# OsuBoard.net
KiCad netlist of a schematic drawn in Altium Designer
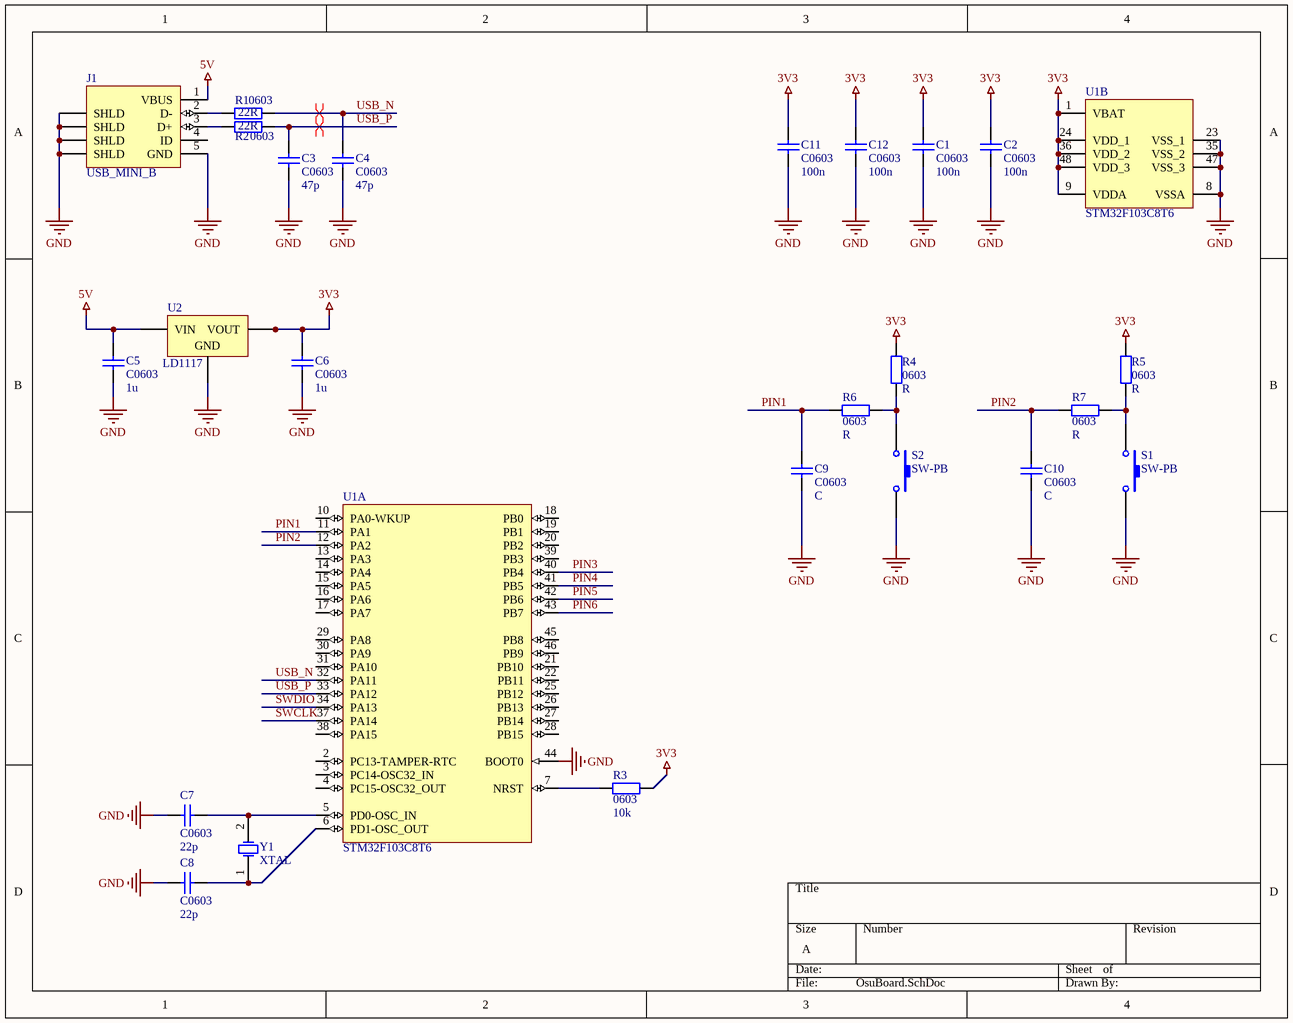
[diagram p0: OsuBoard.SchDoc]

(export (version "E")
  (design (tool "Eeschema 10.0.6"))
  (components
    (comp (ref "C1")
      (value "100n")
      (footprint "C0603")
      (description "Generic capacitor")
      (libsource (lib "_RLC") (part "Cap"))
    )
    (comp (ref "C2")
      (value "100n")
      (footprint "C0603")
      (description "Generic capacitor")
      (libsource (lib "_RLC") (part "Cap"))
    )
    (comp (ref "C3")
      (value "47p")
      (footprint "C0603")
      (description "Generic capacitor")
      (libsource (lib "_RLC") (part "Cap"))
    )
    (comp (ref "C4")
      (value "47p")
      (footprint "C0603")
      (description "Generic capacitor")
      (libsource (lib "_RLC") (part "Cap"))
    )
    (comp (ref "C5")
      (value "1u")
      (footprint "C0603")
      (description "Generic capacitor")
      (libsource (lib "_RLC") (part "Cap"))
    )
    (comp (ref "C6")
      (value "1u")
      (footprint "C0603")
      (description "Generic capacitor")
      (libsource (lib "_RLC") (part "Cap"))
    )
    (comp (ref "C7")
      (value "22p")
      (footprint "C0603")
      (description "Generic capacitor")
      (libsource (lib "_RLC") (part "Cap"))
    )
    (comp (ref "C8")
      (value "22p")
      (footprint "C0603")
      (description "Generic capacitor")
      (libsource (lib "_RLC") (part "Cap"))
    )
    (comp (ref "C9")
      (value "C")
      (footprint "C0603")
      (description "Generic capacitor")
      (libsource (lib "_RLC") (part "Cap"))
    )
    (comp (ref "C10")
      (value "C")
      (footprint "C0603")
      (description "Generic capacitor")
      (libsource (lib "_RLC") (part "Cap"))
    )
    (comp (ref "C11")
      (value "100n")
      (footprint "C0603")
      (description "Generic capacitor")
      (libsource (lib "_RLC") (part "Cap"))
    )
    (comp (ref "C12")
      (value "100n")
      (footprint "C0603")
      (description "Generic capacitor")
      (libsource (lib "_RLC") (part "Cap"))
    )
    (comp (ref "J1")
      (value "USB_MINI_B")
      (footprint "USB_Mini_B_9.3x7.7")
      (description "USB On-The-Go (OTG) Mini-B Receptacle")
      (libsource (lib "_Connectors") (part "USB_MINI_B2"))
    )
    (comp (ref "R1")
      (value "22R")
      (footprint "0603")
      (description "Generic resistor")
      (libsource (lib "") (part "Res_1"))
    )
    (comp (ref "R2")
      (value "22R")
      (footprint "0603")
      (description "Generic resistor")
      (libsource (lib "") (part "Res_1"))
    )
    (comp (ref "R3")
      (value "10k")
      (footprint "0603")
      (description "Generic resistor")
      (libsource (lib "") (part "Res_1"))
    )
    (comp (ref "R4")
      (value "R")
      (footprint "0603")
      (description "Generic resistor")
      (libsource (lib "_RLC") (part "Res"))
    )
    (comp (ref "R5")
      (value "R")
      (footprint "0603")
      (description "Generic resistor")
      (libsource (lib "_RLC") (part "Res"))
    )
    (comp (ref "R6")
      (value "R")
      (footprint "0603")
      (description "Generic resistor")
      (libsource (lib "") (part "Res_1"))
    )
    (comp (ref "R7")
      (value "R")
      (footprint "0603")
      (description "Generic resistor")
      (libsource (lib "") (part "Res_1"))
    )
    (comp (ref "S1")
      (value "SW-PB")
      (footprint "Cherry MX footprint")
      (description "Switch")
      (fields (field (name "PUBLISHER") "Altium Limited"))
      (libsource (lib "Miscellaneous Devices") (part "SW-PB"))
    )
    (comp (ref "S2")
      (value "SW-PB")
      (footprint "Cherry MX footprint")
      (description "Switch")
      (fields (field (name "PUBLISHER") "Altium Limited"))
      (libsource (lib "Miscellaneous Devices") (part "SW-PB"))
    )
    (comp (ref "U1")
      (value "STM32F103C8T6")
      (footprint "QFP_48_0.5_M")
      (libsource (lib "_Microcircuits") (part "STM32F103C8T6"))
    )
    (comp (ref "U2")
      (value "LD1117")
      (footprint "TO-252")
      (description "Low drop positive voltage regulator")
      (libsource (lib "_Microcircuits") (part "LD1117"))
    )
    (comp (ref "Y1")
      (value "XTAL")
      (footprint "HC49")
      (description "Crystal Oscillator")
      (fields (field (name "PUBLISHER") "Altium Limited"))
      (libsource (lib "_Passive") (part "XTAL"))
    )
  )
  (nets
    (net (code "1") (name "/PIN1") (class "Default")
      (node (ref "C9") (pin "1") (pinfunction "1_1") (pintype "passive"))
      (node (ref "R6") (pin "1") (pinfunction "1_1") (pintype "passive"))
      (node (ref "U1") (pin "11") (pinfunction "PA1_11") (pintype "bidirectional"))
    )
    (net (code "2") (name "/PIN2") (class "Default")
      (node (ref "C10") (pin "1") (pinfunction "1_1") (pintype "passive"))
      (node (ref "R7") (pin "1") (pinfunction "1_1") (pintype "passive"))
      (node (ref "U1") (pin "12") (pinfunction "PA2_12") (pintype "bidirectional"))
    )
    (net (code "3") (name "/PIN3") (class "Default")
      (node (ref "U1") (pin "40") (pinfunction "PB4_40") (pintype "bidirectional"))
    )
    (net (code "4") (name "/PIN4") (class "Default")
      (node (ref "U1") (pin "41") (pinfunction "PB5_41") (pintype "bidirectional"))
    )
    (net (code "5") (name "/PIN5") (class "Default")
      (node (ref "U1") (pin "42") (pinfunction "PB6_42") (pintype "bidirectional"))
    )
    (net (code "6") (name "/PIN6") (class "Default")
      (node (ref "U1") (pin "43") (pinfunction "PB7_43") (pintype "bidirectional"))
    )
    (net (code "7") (name "/SWCLK") (class "Default")
      (node (ref "U1") (pin "37") (pinfunction "PA14_37") (pintype "bidirectional"))
    )
    (net (code "8") (name "/SWDIO") (class "Default")
      (node (ref "U1") (pin "34") (pinfunction "PA13_34") (pintype "bidirectional"))
    )
    (net (code "9") (name "/USB_N") (class "Default")
      (node (ref "C4") (pin "1") (pinfunction "1_1") (pintype "passive"))
      (node (ref "R1") (pin "2") (pinfunction "2_2") (pintype "passive"))
      (node (ref "U1") (pin "32") (pinfunction "PA11_32") (pintype "bidirectional"))
    )
    (net (code "10") (name "/USB_P") (class "Default")
      (node (ref "C3") (pin "1") (pinfunction "1_1") (pintype "passive"))
      (node (ref "R2") (pin "2") (pinfunction "2_2") (pintype "passive"))
      (node (ref "U1") (pin "33") (pinfunction "PA12_33") (pintype "bidirectional"))
    )
    (net (code "11") (name "3V3") (class "Default")
      (node (ref "C1") (pin "1") (pinfunction "1_1") (pintype "passive"))
      (node (ref "C11") (pin "1") (pinfunction "1_1") (pintype "passive"))
      (node (ref "C12") (pin "1") (pinfunction "1_1") (pintype "passive"))
      (node (ref "C2") (pin "1") (pinfunction "1_1") (pintype "passive"))
      (node (ref "C6") (pin "1") (pinfunction "1_1") (pintype "passive"))
      (node (ref "R3") (pin "2") (pinfunction "2_2") (pintype "passive"))
      (node (ref "R4") (pin "1") (pinfunction "1_1") (pintype "passive"))
      (node (ref "R5") (pin "1") (pinfunction "1_1") (pintype "passive"))
      (node (ref "U1") (pin "1") (pinfunction "VBAT_1") (pintype "power_in"))
      (node (ref "U1") (pin "24") (pinfunction "VDD_1_24") (pintype "power_in"))
      (node (ref "U1") (pin "36") (pinfunction "VDD_2_36") (pintype "power_in"))
      (node (ref "U1") (pin "48") (pinfunction "VDD_3_48") (pintype "power_in"))
      (node (ref "U1") (pin "9") (pinfunction "VDDA_9") (pintype "power_in"))
      (node (ref "U2") (pin "2") (pinfunction "VOUT_2") (pintype "power_in"))
      (node (ref "U2") (pin "4") (pinfunction "VOUT_4") (pintype "power_in"))
      (node (ref "U2") (pin "5") (pinfunction "VOUT_5") (pintype "power_in"))
      (node (ref "U2") (pin "6") (pinfunction "VOUT_6") (pintype "power_in"))
    )
    (net (code "12") (name "5V") (class "Default")
      (node (ref "C5") (pin "1") (pinfunction "1_1") (pintype "passive"))
      (node (ref "J1") (pin "1") (pinfunction "VBUS_1") (pintype "power_in"))
      (node (ref "U2") (pin "3") (pinfunction "VIN_3") (pintype "power_in"))
    )
    (net (code "13") (name "GND") (class "Default")
      (node (ref "C1") (pin "2") (pinfunction "2_2") (pintype "passive"))
      (node (ref "C10") (pin "2") (pinfunction "2_2") (pintype "passive"))
      (node (ref "C11") (pin "2") (pinfunction "2_2") (pintype "passive"))
      (node (ref "C12") (pin "2") (pinfunction "2_2") (pintype "passive"))
      (node (ref "C2") (pin "2") (pinfunction "2_2") (pintype "passive"))
      (node (ref "C3") (pin "2") (pinfunction "2_2") (pintype "passive"))
      (node (ref "C4") (pin "2") (pinfunction "2_2") (pintype "passive"))
      (node (ref "C5") (pin "2") (pinfunction "2_2") (pintype "passive"))
      (node (ref "C6") (pin "2") (pinfunction "2_2") (pintype "passive"))
      (node (ref "C7") (pin "1") (pinfunction "1_1") (pintype "passive"))
      (node (ref "C8") (pin "1") (pinfunction "1_1") (pintype "passive"))
      (node (ref "C9") (pin "2") (pinfunction "2_2") (pintype "passive"))
      (node (ref "J1") (pin "5") (pinfunction "GND_5") (pintype "power_in"))
      (node (ref "J1") (pin "MH1") (pinfunction "SHLD_MH1") (pintype "passive"))
      (node (ref "J1") (pin "MH2") (pinfunction "SHLD_MH2") (pintype "passive"))
      (node (ref "J1") (pin "MH3") (pinfunction "SHLD_MH3") (pintype "passive"))
      (node (ref "J1") (pin "MH4") (pinfunction "SHLD_MH4") (pintype "passive"))
      (node (ref "S1") (pin "2") (pinfunction "2_2") (pintype "passive"))
      (node (ref "S2") (pin "2") (pinfunction "2_2") (pintype "passive"))
      (node (ref "U1") (pin "23") (pinfunction "VSS_1_23") (pintype "power_in"))
      (node (ref "U1") (pin "35") (pinfunction "VSS_2_35") (pintype "power_in"))
      (node (ref "U1") (pin "44") (pinfunction "BOOT0_44") (pintype "input"))
      (node (ref "U1") (pin "47") (pinfunction "VSS_3_47") (pintype "power_in"))
      (node (ref "U1") (pin "8") (pinfunction "VSSA_8") (pintype "power_in"))
      (node (ref "U2") (pin "1") (pinfunction "GND_1") (pintype "power_in"))
    )
    (net (code "14") (name "Net-(J1-D+)") (class "Default")
      (node (ref "J1") (pin "3") (pinfunction "D+_3") (pintype "bidirectional"))
      (node (ref "R2") (pin "1") (pinfunction "1_1") (pintype "passive"))
    )
    (net (code "15") (name "Net-(J1-D-)") (class "Default")
      (node (ref "J1") (pin "2") (pinfunction "D-_2") (pintype "bidirectional"))
      (node (ref "R1") (pin "1") (pinfunction "1_1") (pintype "passive"))
    )
    (net (code "16") (name "Net-(R4-Pad2)") (class "Default")
      (node (ref "R4") (pin "2") (pinfunction "2_2") (pintype "passive"))
      (node (ref "R6") (pin "2") (pinfunction "2_2") (pintype "passive"))
      (node (ref "S2") (pin "1") (pinfunction "1_1") (pintype "passive"))
    )
    (net (code "17") (name "Net-(R5-Pad2)") (class "Default")
      (node (ref "R5") (pin "2") (pinfunction "2_2") (pintype "passive"))
      (node (ref "R7") (pin "2") (pinfunction "2_2") (pintype "passive"))
      (node (ref "S1") (pin "1") (pinfunction "1_1") (pintype "passive"))
    )
    (net (code "18") (name "Net-(U1A-NRST)") (class "Default")
      (node (ref "R3") (pin "1") (pinfunction "1_1") (pintype "passive"))
      (node (ref "U1") (pin "7") (pinfunction "NRST_7") (pintype "bidirectional"))
    )
    (net (code "19") (name "Net-(U1A-PD0-OSC_IN)") (class "Default")
      (node (ref "C7") (pin "2") (pinfunction "2_2") (pintype "passive"))
      (node (ref "U1") (pin "5") (pinfunction "PD0-OSC_IN_5") (pintype "bidirectional"))
      (node (ref "Y1") (pin "2") (pinfunction "OSC2_2") (pintype "passive"))
    )
    (net (code "20") (name "Net-(U1A-PD1-OSC_OUT)") (class "Default")
      (node (ref "C8") (pin "2") (pinfunction "2_2") (pintype "passive"))
      (node (ref "U1") (pin "6") (pinfunction "PD1-OSC_OUT_6") (pintype "bidirectional"))
      (node (ref "Y1") (pin "1") (pinfunction "OSC1_1") (pintype "passive"))
    )
    (net (code "21") (name "unconnected-(J1-ID-Pad4)") (class "Default")
      (node (ref "J1") (pin "4") (pinfunction "ID_4") (pintype "passive"))
    )
    (net (code "22") (name "unconnected-(U1A-PA0-WKUP-Pad10)") (class "Default")
      (node (ref "U1") (pin "10") (pinfunction "PA0-WKUP_10") (pintype "bidirectional"))
    )
    (net (code "23") (name "unconnected-(U1A-PA3-Pad13)") (class "Default")
      (node (ref "U1") (pin "13") (pinfunction "PA3_13") (pintype "bidirectional"))
    )
    (net (code "24") (name "unconnected-(U1A-PA4-Pad14)") (class "Default")
      (node (ref "U1") (pin "14") (pinfunction "PA4_14") (pintype "bidirectional"))
    )
    (net (code "25") (name "unconnected-(U1A-PA5-Pad15)") (class "Default")
      (node (ref "U1") (pin "15") (pinfunction "PA5_15") (pintype "bidirectional"))
    )
    (net (code "26") (name "unconnected-(U1A-PA6-Pad16)") (class "Default")
      (node (ref "U1") (pin "16") (pinfunction "PA6_16") (pintype "bidirectional"))
    )
    (net (code "27") (name "unconnected-(U1A-PA7-Pad17)") (class "Default")
      (node (ref "U1") (pin "17") (pinfunction "PA7_17") (pintype "bidirectional"))
    )
    (net (code "28") (name "unconnected-(U1A-PA8-Pad29)") (class "Default")
      (node (ref "U1") (pin "29") (pinfunction "PA8_29") (pintype "bidirectional"))
    )
    (net (code "29") (name "unconnected-(U1A-PA9-Pad30)") (class "Default")
      (node (ref "U1") (pin "30") (pinfunction "PA9_30") (pintype "bidirectional"))
    )
    (net (code "30") (name "unconnected-(U1A-PA10-Pad31)") (class "Default")
      (node (ref "U1") (pin "31") (pinfunction "PA10_31") (pintype "bidirectional"))
    )
    (net (code "31") (name "unconnected-(U1A-PA15-Pad38)") (class "Default")
      (node (ref "U1") (pin "38") (pinfunction "PA15_38") (pintype "bidirectional"))
    )
    (net (code "32") (name "unconnected-(U1A-PB0-Pad18)") (class "Default")
      (node (ref "U1") (pin "18") (pinfunction "PB0_18") (pintype "bidirectional"))
    )
    (net (code "33") (name "unconnected-(U1A-PB1-Pad19)") (class "Default")
      (node (ref "U1") (pin "19") (pinfunction "PB1_19") (pintype "bidirectional"))
    )
    (net (code "34") (name "unconnected-(U1A-PB2-Pad20)") (class "Default")
      (node (ref "U1") (pin "20") (pinfunction "PB2_20") (pintype "bidirectional"))
    )
    (net (code "35") (name "unconnected-(U1A-PB3-Pad39)") (class "Default")
      (node (ref "U1") (pin "39") (pinfunction "PB3_39") (pintype "bidirectional"))
    )
    (net (code "36") (name "unconnected-(U1A-PB8-Pad45)") (class "Default")
      (node (ref "U1") (pin "45") (pinfunction "PB8_45") (pintype "bidirectional"))
    )
    (net (code "37") (name "unconnected-(U1A-PB9-Pad46)") (class "Default")
      (node (ref "U1") (pin "46") (pinfunction "PB9_46") (pintype "bidirectional"))
    )
    (net (code "38") (name "unconnected-(U1A-PB10-Pad21)") (class "Default")
      (node (ref "U1") (pin "21") (pinfunction "PB10_21") (pintype "bidirectional"))
    )
    (net (code "39") (name "unconnected-(U1A-PB11-Pad22)") (class "Default")
      (node (ref "U1") (pin "22") (pinfunction "PB11_22") (pintype "bidirectional"))
    )
    (net (code "40") (name "unconnected-(U1A-PB12-Pad25)") (class "Default")
      (node (ref "U1") (pin "25") (pinfunction "PB12_25") (pintype "bidirectional"))
    )
    (net (code "41") (name "unconnected-(U1A-PB13-Pad26)") (class "Default")
      (node (ref "U1") (pin "26") (pinfunction "PB13_26") (pintype "bidirectional"))
    )
    (net (code "42") (name "unconnected-(U1A-PB14-Pad27)") (class "Default")
      (node (ref "U1") (pin "27") (pinfunction "PB14_27") (pintype "bidirectional"))
    )
    (net (code "43") (name "unconnected-(U1A-PB15-Pad28)") (class "Default")
      (node (ref "U1") (pin "28") (pinfunction "PB15_28") (pintype "bidirectional"))
    )
    (net (code "44") (name "unconnected-(U1A-PC13-TAMPER-RTC-Pad2)") (class "Default")
      (node (ref "U1") (pin "2") (pinfunction "PC13-TAMPER-RTC_2") (pintype "bidirectional"))
    )
    (net (code "45") (name "unconnected-(U1A-PC14-OSC32_IN-Pad3)") (class "Default")
      (node (ref "U1") (pin "3") (pinfunction "PC14-OSC32_IN_3") (pintype "bidirectional"))
    )
    (net (code "46") (name "unconnected-(U1A-PC15-OSC32_OUT-Pad4)") (class "Default")
      (node (ref "U1") (pin "4") (pinfunction "PC15-OSC32_OUT_4") (pintype "bidirectional"))
    )
  )
)
